# DS18B20example3.net
KiCad netlist of a schematic drawn in EAGLE
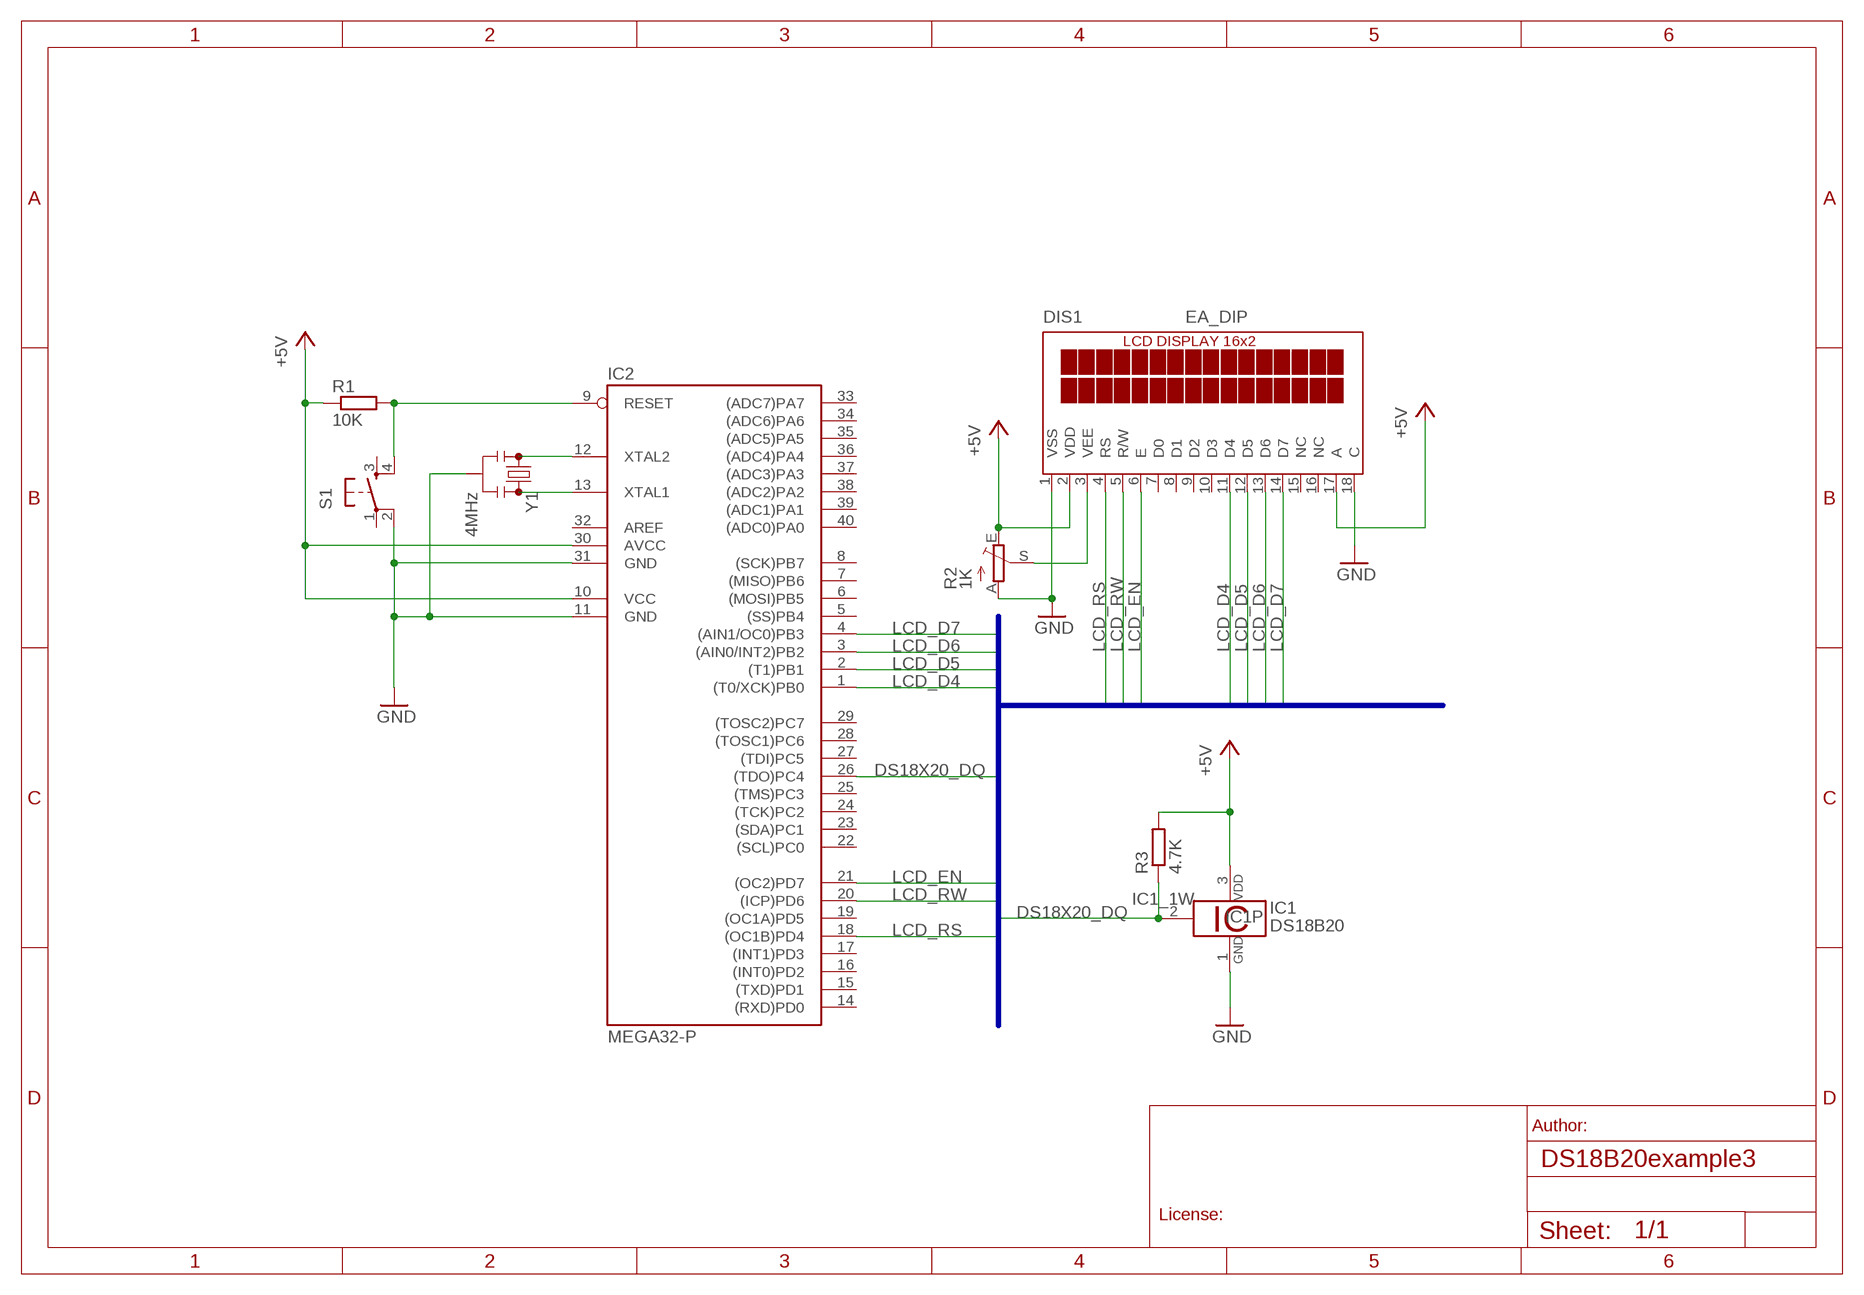
[diagram p0: schematic, sheet 1]

(export (version "E")
  (design (tool "Eeschema 10.0.6"))
  (components
    (comp (ref "DIS1")
      (value "EA_DIP")
      (footprint "eagle-import:EA_DIP")
      (libsource (lib "eagle-import") (part "EA_DIP"))
    )
    (comp (ref "IC1")
      (value "DS18B20")
      (footprint "eagle-import:TO92-")
      (libsource (lib "eagle-import") (part "DS18B20"))
    )
    (comp (ref "IC2")
      (value "MEGA32-P")
      (footprint "eagle-import:DIL40")
      (fields (field (name "MPN") "ATMEGA32-16PU"))
      (libsource (lib "eagle-import") (part "MEGA32-P"))
    )
    (comp (ref "R1")
      (value "10K")
      (footprint "eagle-import:0204_7")
      (libsource (lib "eagle-import") (part "R-EU_0204/7"))
    )
    (comp (ref "R2")
      (value "1K")
      (footprint "eagle-import:B25P")
      (libsource (lib "eagle-import") (part "TRIM_EU-B25P"))
    )
    (comp (ref "R3")
      (value "4.7K")
      (footprint "eagle-import:0204_7")
      (libsource (lib "eagle-import") (part "R-EU_0204/7"))
    )
    (comp (ref "S1")
      (value "TAC_SWITCHPTH")
      (footprint "eagle-import:TACTILE-PTH")
      (libsource (lib "eagle-import") (part "TAC_SWITCHPTH"))
    )
    (comp (ref "Y1")
      (value "4MHz")
      (footprint "eagle-import:RESONATOR-PTH")
      (libsource (lib "eagle-import") (part "RESONATORPTH"))
    )
  )
  (nets
    (net (code "1") (name "+5V") (class "Default")
      (node (ref "DIS1") (pin "17") (pinfunction "A_17") (pintype "passive"))
      (node (ref "DIS1") (pin "2") (pinfunction "VDD_2") (pintype "power_in"))
      (node (ref "IC1") (pin "3") (pinfunction "VDD_3") (pintype "power_in"))
      (node (ref "IC2") (pin "10") (pinfunction "VCC_10") (pintype "power_in"))
      (node (ref "IC2") (pin "30") (pinfunction "AVCC_30") (pintype "power_in"))
      (node (ref "R1") (pin "1") (pinfunction "1_1") (pintype "passive"))
      (node (ref "R2") (pin "E") (pinfunction "E_E") (pintype "passive"))
      (node (ref "R3") (pin "2") (pinfunction "2_2") (pintype "passive"))
    )
    (net (code "2") (name "/DS18X20_DQ") (class "Default")
      (node (ref "IC1") (pin "2") (pinfunction "1W_2") (pintype "power_in"))
      (node (ref "IC2") (pin "26") (pinfunction "(TDO)PC4_26") (pintype "bidirectional"))
      (node (ref "R3") (pin "1") (pinfunction "1_1") (pintype "passive"))
    )
    (net (code "3") (name "/LCD_D4") (class "Default")
      (node (ref "DIS1") (pin "11") (pinfunction "D4_11") (pintype "input"))
      (node (ref "IC2") (pin "1") (pinfunction "(T0/XCK)PB0_1") (pintype "bidirectional"))
    )
    (net (code "4") (name "/LCD_D5") (class "Default")
      (node (ref "DIS1") (pin "12") (pinfunction "D5_12") (pintype "input"))
      (node (ref "IC2") (pin "2") (pinfunction "(T1)PB1_2") (pintype "bidirectional"))
    )
    (net (code "5") (name "/LCD_D6") (class "Default")
      (node (ref "DIS1") (pin "13") (pinfunction "D6_13") (pintype "input"))
      (node (ref "IC2") (pin "3") (pinfunction "(AIN0/INT2)PB2_3") (pintype "bidirectional"))
    )
    (net (code "6") (name "/LCD_D7") (class "Default")
      (node (ref "DIS1") (pin "14") (pinfunction "D7_14") (pintype "input"))
      (node (ref "IC2") (pin "4") (pinfunction "(AIN1/OC0)PB3_4") (pintype "bidirectional"))
    )
    (net (code "7") (name "/LCD_EN") (class "Default")
      (node (ref "DIS1") (pin "6") (pinfunction "E_6") (pintype "input"))
      (node (ref "IC2") (pin "21") (pinfunction "(OC2)PD7_21") (pintype "bidirectional"))
    )
    (net (code "8") (name "/LCD_RS") (class "Default")
      (node (ref "DIS1") (pin "4") (pinfunction "RS_4") (pintype "input"))
      (node (ref "IC2") (pin "18") (pinfunction "(OC1B)PD4_18") (pintype "bidirectional"))
    )
    (net (code "9") (name "/LCD_RW") (class "Default")
      (node (ref "DIS1") (pin "5") (pinfunction "R/W_5") (pintype "input"))
      (node (ref "IC2") (pin "20") (pinfunction "(ICP)PD6_20") (pintype "bidirectional"))
    )
    (net (code "10") (name "GND") (class "Default")
      (node (ref "DIS1") (pin "1") (pinfunction "VSS_1") (pintype "power_in"))
      (node (ref "DIS1") (pin "18") (pinfunction "C_18") (pintype "passive"))
      (node (ref "IC1") (pin "1") (pinfunction "GND_1") (pintype "power_in"))
      (node (ref "IC2") (pin "11") (pinfunction "GND_11") (pintype "power_in"))
      (node (ref "IC2") (pin "31") (pinfunction "GND_31") (pintype "power_in"))
      (node (ref "R2") (pin "A") (pinfunction "A_A") (pintype "passive"))
      (node (ref "S1") (pin "2") (pinfunction "2_2") (pintype "passive"))
      (node (ref "Y1") (pin "2") (pinfunction "2_2") (pintype "passive"))
    )
    (net (code "11") (name "Net-(DIS1-VEE)") (class "Default")
      (node (ref "DIS1") (pin "3") (pinfunction "VEE_3") (pintype "power_in"))
      (node (ref "R2") (pin "S") (pinfunction "S_S") (pintype "passive"))
    )
    (net (code "12") (name "Net-(IC2-RESET)") (class "Default")
      (node (ref "IC2") (pin "9") (pinfunction "RESET_9") (pintype "input"))
      (node (ref "R1") (pin "2") (pinfunction "2_2") (pintype "passive"))
      (node (ref "S1") (pin "4") (pinfunction "4_4") (pintype "passive"))
    )
    (net (code "13") (name "Net-(IC2-XTAL1)") (class "Default")
      (node (ref "IC2") (pin "13") (pinfunction "XTAL1_13") (pintype "bidirectional"))
      (node (ref "Y1") (pin "3") (pinfunction "3_3") (pintype "passive"))
    )
    (net (code "14") (name "Net-(IC2-XTAL2)") (class "Default")
      (node (ref "IC2") (pin "12") (pinfunction "XTAL2_12") (pintype "bidirectional"))
      (node (ref "Y1") (pin "1") (pinfunction "1_1") (pintype "passive"))
    )
    (net (code "15") (name "unconnected-(DIS1-D0-Pad7)") (class "Default")
      (node (ref "DIS1") (pin "7") (pinfunction "D0_7") (pintype "input"))
    )
    (net (code "16") (name "unconnected-(DIS1-D1-Pad8)") (class "Default")
      (node (ref "DIS1") (pin "8") (pinfunction "D1_8") (pintype "input"))
    )
    (net (code "17") (name "unconnected-(DIS1-D2-Pad9)") (class "Default")
      (node (ref "DIS1") (pin "9") (pinfunction "D2_9") (pintype "input"))
    )
    (net (code "18") (name "unconnected-(DIS1-D3-Pad10)") (class "Default")
      (node (ref "DIS1") (pin "10") (pinfunction "D3_10") (pintype "input"))
    )
    (net (code "19") (name "unconnected-(DIS1-NC-Pad15)") (class "Default")
      (node (ref "DIS1") (pin "15") (pinfunction "NC_15") (pintype "no_connect"))
    )
    (net (code "20") (name "unconnected-(DIS1-NC-Pad16)") (class "Default")
      (node (ref "DIS1") (pin "16") (pinfunction "NC_16") (pintype "no_connect"))
    )
    (net (code "21") (name "unconnected-(IC2-(ADC0)PA0-Pad40)") (class "Default")
      (node (ref "IC2") (pin "40") (pinfunction "(ADC0)PA0_40") (pintype "bidirectional"))
    )
    (net (code "22") (name "unconnected-(IC2-(ADC1)PA1-Pad39)") (class "Default")
      (node (ref "IC2") (pin "39") (pinfunction "(ADC1)PA1_39") (pintype "bidirectional"))
    )
    (net (code "23") (name "unconnected-(IC2-(ADC2)PA2-Pad38)") (class "Default")
      (node (ref "IC2") (pin "38") (pinfunction "(ADC2)PA2_38") (pintype "bidirectional"))
    )
    (net (code "24") (name "unconnected-(IC2-(ADC3)PA3-Pad37)") (class "Default")
      (node (ref "IC2") (pin "37") (pinfunction "(ADC3)PA3_37") (pintype "bidirectional"))
    )
    (net (code "25") (name "unconnected-(IC2-(ADC4)PA4-Pad36)") (class "Default")
      (node (ref "IC2") (pin "36") (pinfunction "(ADC4)PA4_36") (pintype "bidirectional"))
    )
    (net (code "26") (name "unconnected-(IC2-(ADC5)PA5-Pad35)") (class "Default")
      (node (ref "IC2") (pin "35") (pinfunction "(ADC5)PA5_35") (pintype "bidirectional"))
    )
    (net (code "27") (name "unconnected-(IC2-(ADC6)PA6-Pad34)") (class "Default")
      (node (ref "IC2") (pin "34") (pinfunction "(ADC6)PA6_34") (pintype "bidirectional"))
    )
    (net (code "28") (name "unconnected-(IC2-(ADC7)PA7-Pad33)") (class "Default")
      (node (ref "IC2") (pin "33") (pinfunction "(ADC7)PA7_33") (pintype "bidirectional"))
    )
    (net (code "29") (name "unconnected-(IC2-(INT0)PD2-Pad16)") (class "Default")
      (node (ref "IC2") (pin "16") (pinfunction "(INT0)PD2_16") (pintype "bidirectional"))
    )
    (net (code "30") (name "unconnected-(IC2-(INT1)PD3-Pad17)") (class "Default")
      (node (ref "IC2") (pin "17") (pinfunction "(INT1)PD3_17") (pintype "bidirectional"))
    )
    (net (code "31") (name "unconnected-(IC2-(MISO)PB6-Pad7)") (class "Default")
      (node (ref "IC2") (pin "7") (pinfunction "(MISO)PB6_7") (pintype "bidirectional"))
    )
    (net (code "32") (name "unconnected-(IC2-(MOSI)PB5-Pad6)") (class "Default")
      (node (ref "IC2") (pin "6") (pinfunction "(MOSI)PB5_6") (pintype "bidirectional"))
    )
    (net (code "33") (name "unconnected-(IC2-(OC1A)PD5-Pad19)") (class "Default")
      (node (ref "IC2") (pin "19") (pinfunction "(OC1A)PD5_19") (pintype "bidirectional"))
    )
    (net (code "34") (name "unconnected-(IC2-(RXD)PD0-Pad14)") (class "Default")
      (node (ref "IC2") (pin "14") (pinfunction "(RXD)PD0_14") (pintype "bidirectional"))
    )
    (net (code "35") (name "unconnected-(IC2-(SCK)PB7-Pad8)") (class "Default")
      (node (ref "IC2") (pin "8") (pinfunction "(SCK)PB7_8") (pintype "bidirectional"))
    )
    (net (code "36") (name "unconnected-(IC2-(SCL)PC0-Pad22)") (class "Default")
      (node (ref "IC2") (pin "22") (pinfunction "(SCL)PC0_22") (pintype "bidirectional"))
    )
    (net (code "37") (name "unconnected-(IC2-(SDA)PC1-Pad23)") (class "Default")
      (node (ref "IC2") (pin "23") (pinfunction "(SDA)PC1_23") (pintype "bidirectional"))
    )
    (net (code "38") (name "unconnected-(IC2-(SS)PB4-Pad5)") (class "Default")
      (node (ref "IC2") (pin "5") (pinfunction "(SS)PB4_5") (pintype "bidirectional"))
    )
    (net (code "39") (name "unconnected-(IC2-(TCK)PC2-Pad24)") (class "Default")
      (node (ref "IC2") (pin "24") (pinfunction "(TCK)PC2_24") (pintype "bidirectional"))
    )
    (net (code "40") (name "unconnected-(IC2-(TDI)PC5-Pad27)") (class "Default")
      (node (ref "IC2") (pin "27") (pinfunction "(TDI)PC5_27") (pintype "bidirectional"))
    )
    (net (code "41") (name "unconnected-(IC2-(TMS)PC3-Pad25)") (class "Default")
      (node (ref "IC2") (pin "25") (pinfunction "(TMS)PC3_25") (pintype "bidirectional"))
    )
    (net (code "42") (name "unconnected-(IC2-(TOSC1)PC6-Pad28)") (class "Default")
      (node (ref "IC2") (pin "28") (pinfunction "(TOSC1)PC6_28") (pintype "bidirectional"))
    )
    (net (code "43") (name "unconnected-(IC2-(TOSC2)PC7-Pad29)") (class "Default")
      (node (ref "IC2") (pin "29") (pinfunction "(TOSC2)PC7_29") (pintype "bidirectional"))
    )
    (net (code "44") (name "unconnected-(IC2-(TXD)PD1-Pad15)") (class "Default")
      (node (ref "IC2") (pin "15") (pinfunction "(TXD)PD1_15") (pintype "bidirectional"))
    )
    (net (code "45") (name "unconnected-(IC2-AREF-Pad32)") (class "Default")
      (node (ref "IC2") (pin "32") (pinfunction "AREF_32") (pintype "passive"))
    )
    (net (code "46") (name "unconnected-(S1-Pad1)") (class "Default")
      (node (ref "S1") (pin "1") (pinfunction "1_1") (pintype "passive"))
    )
    (net (code "47") (name "unconnected-(S1-Pad3)") (class "Default")
      (node (ref "S1") (pin "3") (pinfunction "3_3") (pintype "passive"))
    )
  )
)
